# Perifericos.net
KiCad netlist of a schematic drawn in Altium Designer
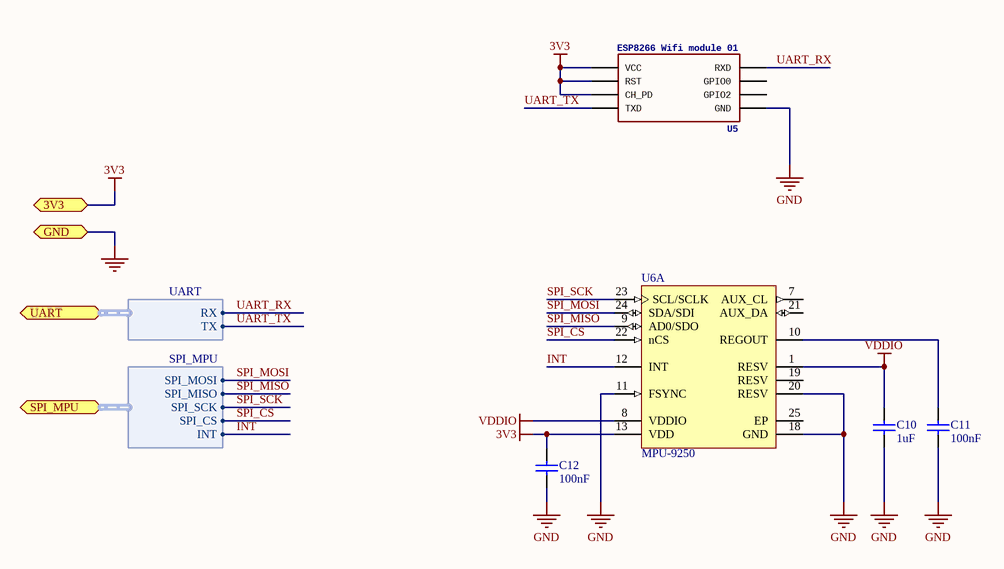
[diagram p0: Perifericos.SchDoc]

(export (version "E")
  (design (tool "Eeschema 10.0.6"))
  (components
    (comp (ref "C10")
      (value "1uF")
      (footprint "CAPC0603(1608)100_L")
      (description "CAP 1uF 25V ±10% 0603 (1608 Metric) Thickness 1mm SMD")
      (fields (field (name "TOLERANCE") "Â±10%"))
      (libsource (lib "Altium Content Vault") (part "CMP-1035-02740-1"))
    )
    (comp (ref "C11")
      (value "100nF")
      (footprint "CAPC0402(1005)60_L")
      (description "CAP 100nF 25V ±10% 0402 (1005 Metric) Thickness 0.6mm SMD")
      (fields (field (name "TOLERANCE") "Â±10%"))
      (libsource (lib "Altium Content Vault") (part "CMP-1034-02072-1"))
    )
    (comp (ref "C12")
      (value "100nF")
      (footprint "CAPC0402(1005)60_L")
      (description "CAP 100nF 25V ±10% 0402 (1005 Metric) Thickness 0.6mm SMD")
      (fields (field (name "TOLERANCE") "Â±10%"))
      (libsource (lib "Altium Content Vault") (part "CMP-1034-02072-1"))
    )
    (comp (ref "U5")
      (value "ESP8266 Wifi module 01")
      (footprint "ESP01")
      (libsource (lib "esp8266modules") (part "ESP01"))
    )
    (comp (ref "U6")
      (value "MPU-9250")
      (footprint "INSE-QFN-24-1700X1540TP_L")
      (description "9-axis MotionTracking device, 2.4 to 3,6 V, -40 to 85 degC, 24-Pin QFN, RoHS, Tape and Reel")
      (fields (field (name "MANUFACTURER") "InvenSense"))
      (libsource (lib "MPU-9250") (part "CMP-2100-03657-1"))
    )
  )
  (nets
    (net (code "3") (name "/INT") (class "Default")
      (node (ref "U6") (pin "12") (pinfunction "INT_12") (pintype "tri_state"))
    )
    (net (code "4") (name "/SPI_CS") (class "Default")
      (node (ref "U6") (pin "22") (pinfunction "nCS_22") (pintype "input"))
    )
    (net (code "5") (name "/SPI_MISO") (class "Default")
      (node (ref "U6") (pin "9") (pinfunction "AD0/SDO_9") (pintype "bidirectional"))
    )
    (net (code "6") (name "/SPI_MOSI") (class "Default")
      (node (ref "U6") (pin "24") (pinfunction "SDA/SDI_24") (pintype "bidirectional"))
    )
    (net (code "7") (name "/SPI_SCK") (class "Default")
      (node (ref "U6") (pin "23") (pinfunction "SCL/SCLK_23") (pintype "input"))
    )
    (net (code "8") (name "/UART_RX") (class "Default")
      (node (ref "U5") (pin "RX") (pinfunction "RXD_RX") (pintype "passive"))
    )
    (net (code "9") (name "/UART_TX") (class "Default")
      (node (ref "U5") (pin "TX") (pinfunction "TXD_TX") (pintype "passive"))
    )
    (net (code "12") (name "0") (class "Default")
      (node (ref "C10") (pin "1") (pinfunction "1_1") (pintype "passive"))
      (node (ref "C11") (pin "1") (pinfunction "1_1") (pintype "passive"))
      (node (ref "C12") (pin "1") (pinfunction "1_1") (pintype "passive"))
      (node (ref "U5") (pin "GND") (pinfunction "GND_GND") (pintype "passive"))
      (node (ref "U6") (pin "11") (pinfunction "FSYNC_11") (pintype "input"))
      (node (ref "U6") (pin "18") (pinfunction "GND_18") (pintype "power_in"))
      (node (ref "U6") (pin "20") (pinfunction "RESV_20") (pintype "power_in"))
    )
    (net (code "13") (name "3V3") (class "Default")
      (node (ref "C12") (pin "2") (pinfunction "2_2") (pintype "passive"))
      (node (ref "U5") (pin "CH_PD") (pinfunction "CH_PD_CH_PD") (pintype "passive"))
      (node (ref "U5") (pin "RST") (pinfunction "RST_RST") (pintype "passive"))
      (node (ref "U5") (pin "VCC") (pinfunction "VCC_VCC") (pintype "passive"))
      (node (ref "U6") (pin "13") (pinfunction "VDD_13") (pintype "power_in"))
    )
    (net (code "14") (name "Net-(U6A-REGOUT)") (class "Default")
      (node (ref "C11") (pin "2") (pinfunction "2_2") (pintype "passive"))
      (node (ref "U6") (pin "10") (pinfunction "REGOUT_10") (pintype "passive"))
    )
    (net (code "15") (name "VDDIO") (class "Default")
      (node (ref "C10") (pin "2") (pinfunction "2_2") (pintype "passive"))
      (node (ref "U6") (pin "1") (pinfunction "RESV_1") (pintype "power_in"))
      (node (ref "U6") (pin "8") (pinfunction "VDDIO_8") (pintype "power_in"))
    )
    (net (code "16") (name "unconnected-(U5-PadGPIO0)") (class "Default")
      (node (ref "U5") (pin "GPIO0") (pinfunction "GPIO0_GPIO0") (pintype "passive"))
    )
    (net (code "17") (name "unconnected-(U5-PadGPIO2)") (class "Default")
      (node (ref "U5") (pin "GPIO2") (pinfunction "GPIO2_GPIO2") (pintype "passive"))
    )
    (net (code "18") (name "unconnected-(U6A-AUX_CL-Pad7)") (class "Default")
      (node (ref "U6") (pin "7") (pinfunction "AUX_CL_7") (pintype "output"))
    )
    (net (code "19") (name "unconnected-(U6A-AUX_DA-Pad21)") (class "Default")
      (node (ref "U6") (pin "21") (pinfunction "AUX_DA_21") (pintype "bidirectional"))
    )
    (net (code "20") (name "unconnected-(U6A-EP-Pad25)") (class "Default")
      (node (ref "U6") (pin "25") (pinfunction "EP_25") (pintype "passive"))
    )
    (net (code "21") (name "unconnected-(U6A-RESV-Pad19)") (class "Default")
      (node (ref "U6") (pin "19") (pinfunction "RESV_19") (pintype "passive"))
    )
  )
)
